# untitled.net
KiCad netlist of a schematic drawn in EAGLE
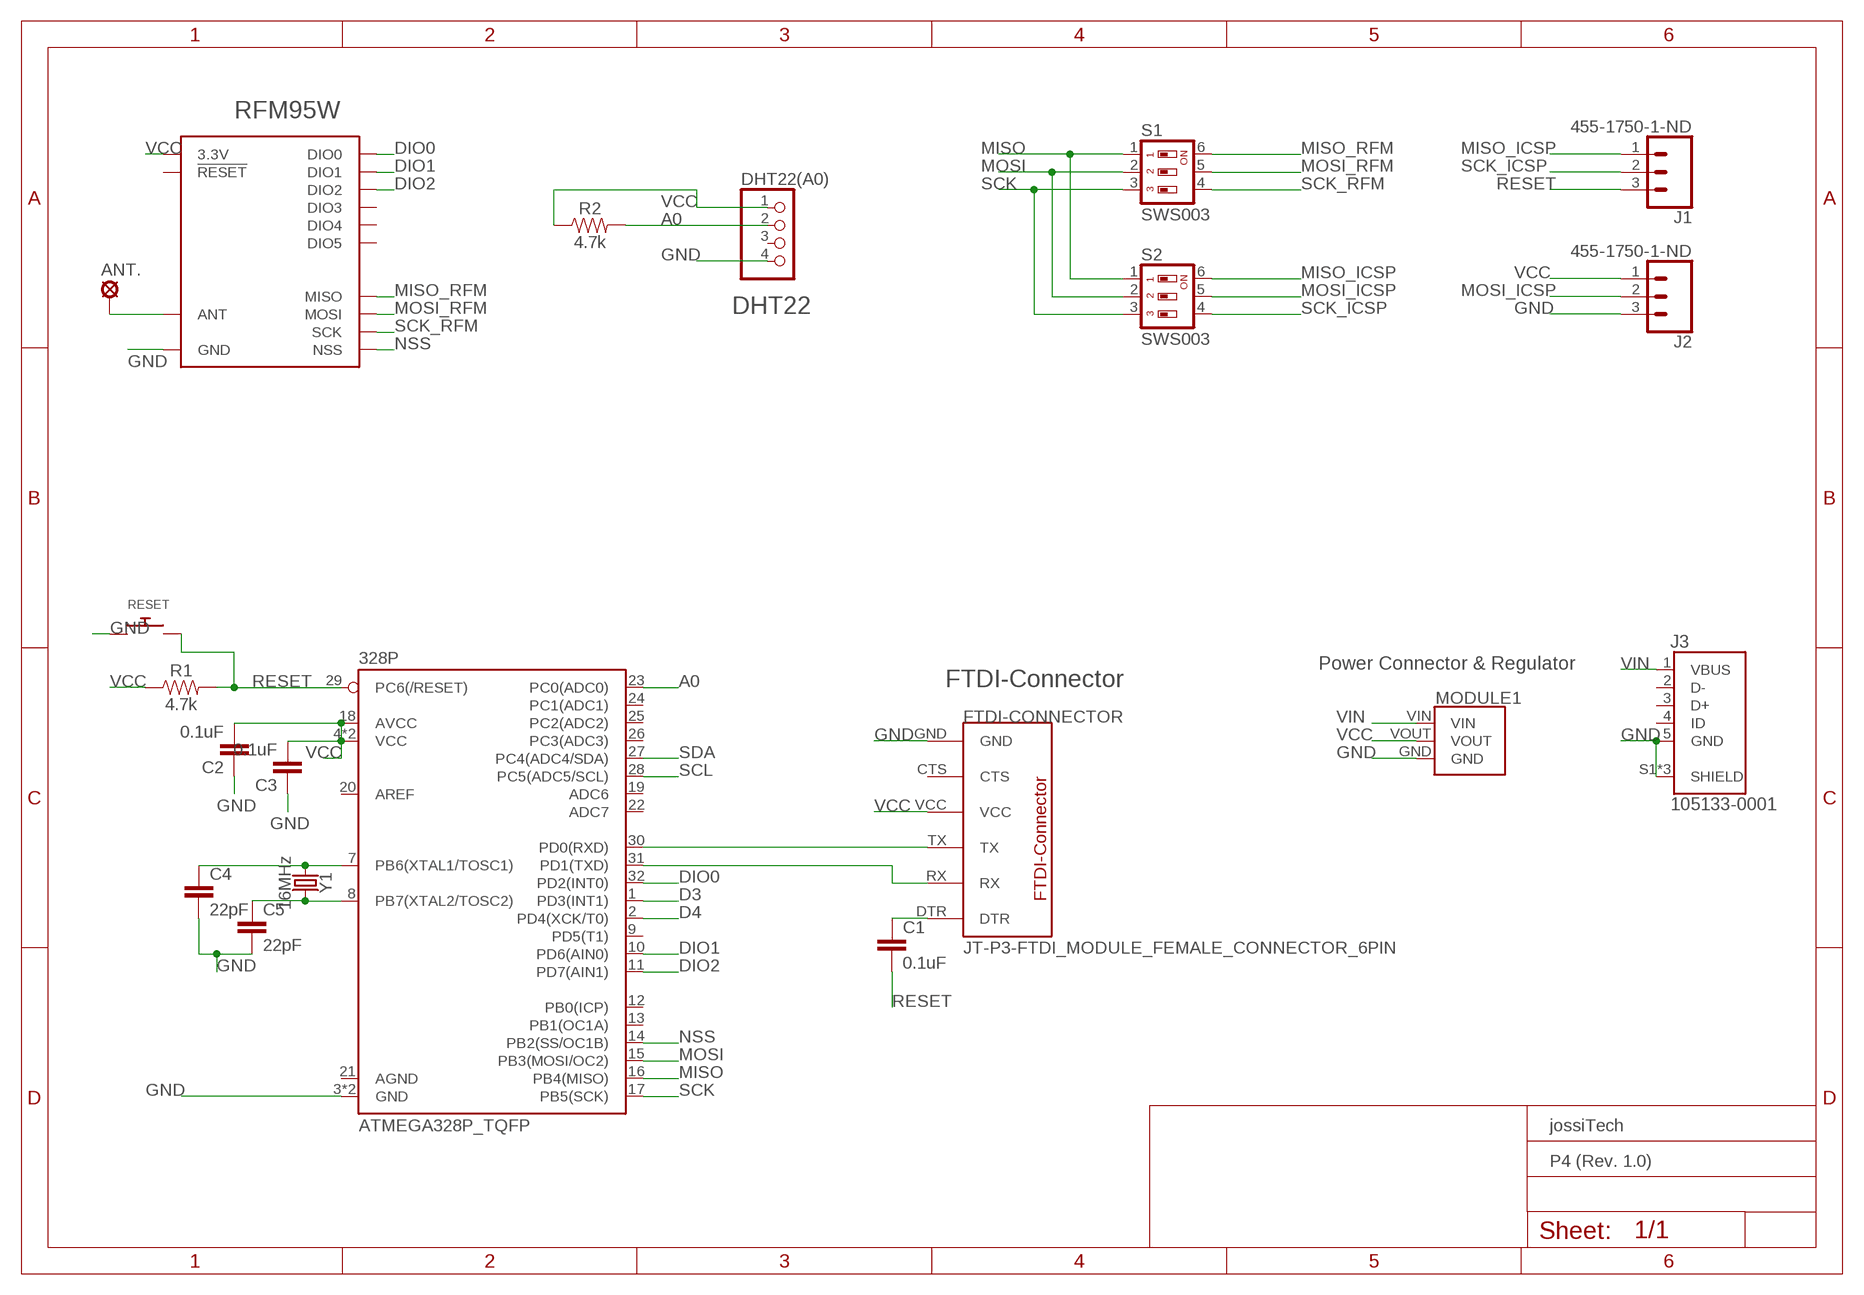
[diagram p0: schematic, sheet 1]

(export (version "E")
  (design (tool "Eeschema 10.0.6"))
  (components
    (comp (ref "328P")
      (value "ATMEGA328P_TQFP")
      (footprint "eagle-import:TQFP32-08")
      (libsource (lib "eagle-import") (part "ATMEGA328P_TQFP"))
    )
    (comp (ref "ANT.")
      (value "LSP11")
      (footprint "eagle-import:LSP11")
      (libsource (lib "eagle-import") (part "LSP11"))
    )
    (comp (ref "C1")
      (value "0.1uF")
      (footprint "eagle-import:0603")
      (libsource (lib "eagle-import") (part "0.1UF-0603-25V-(+80/-20%)"))
    )
    (comp (ref "C2")
      (value "0.1uF")
      (footprint "eagle-import:0603")
      (libsource (lib "eagle-import") (part "0.1UF-0603-25V-(+80/-20%)"))
    )
    (comp (ref "C3")
      (value "0.1uF")
      (footprint "eagle-import:0603")
      (libsource (lib "eagle-import") (part "0.1UF-0603-25V-(+80/-20%)"))
    )
    (comp (ref "C4")
      (value "22pF")
      (footprint "eagle-import:0603")
      (libsource (lib "eagle-import") (part "22PF-0603-50V-5%"))
    )
    (comp (ref "C5")
      (value "22pF")
      (footprint "eagle-import:0603")
      (libsource (lib "eagle-import") (part "22PF-0603-50V-5%"))
    )
    (comp (ref "DHT22(A0)")
      (value "PINHD-1X4")
      (footprint "eagle-import:1X04")
      (libsource (lib "eagle-import") (part "PINHD-1X4"))
    )
    (comp (ref "FTDI-CONNECTOR")
      (value "JT-P3-FTDI_MODULE_FEMALE_CONNECTOR_6PIN")
      (footprint "eagle-import:JT-P3-FTDI_MODULE_FEMALE_CONNECTOR_6PIN")
      (libsource (lib "eagle-import") (part "JT-P3-FTDI_MODULE_FEMALE_CONNECTOR_6PIN"))
    )
    (comp (ref "J1")
      (value "455-1750-1-ND")
      (footprint "eagle-import:1X03")
      (libsource (lib "eagle-import") (part "CONN_03"))
    )
    (comp (ref "J2")
      (value "455-1750-1-ND")
      (footprint "eagle-import:1X03")
      (libsource (lib "eagle-import") (part "CONN_03"))
    )
    (comp (ref "J3")
      (value "105133-0001")
      (footprint "eagle-import:MOLEX_105133-0001")
      (fields (field (name "MF") "Molex"))
      (libsource (lib "eagle-import") (part "105133-0001"))
    )
    (comp (ref "MODULE1")
      (value "JT-P3-VOLTAGEREGULATOR")
      (footprint "eagle-import:JT-P3-VOLTAGEREGULATOR")
      (libsource (lib "eagle-import") (part "JT-P3-VOLTAGEREGULATOR"))
    )
    (comp (ref "R1")
      (value "4.7k")
      (footprint "eagle-import:0603")
      (libsource (lib "eagle-import") (part "4.7KOHM-0603-1/10W-1%"))
    )
    (comp (ref "R2")
      (value "4.7k")
      (footprint "eagle-import:0603")
      (libsource (lib "eagle-import") (part "4.7KOHM-0603-1/10W-1%"))
    )
    (comp (ref "RESET")
      (value "SWITCH_PUSHBUTTONEVQ-PE")
      (footprint "eagle-import:TACT_PANA-EVQ")
      (libsource (lib "eagle-import") (part "SWITCH_PUSHBUTTONEVQ-PE"))
    )
    (comp (ref "S1")
      (value "SWS003")
      (footprint "eagle-import:SMS-003")
      (libsource (lib "eagle-import") (part "SWS003"))
    )
    (comp (ref "S2")
      (value "SWS003")
      (footprint "eagle-import:SMS-003")
      (libsource (lib "eagle-import") (part "SWS003"))
    )
    (comp (ref "U2")
      (value "RFM95W")
      (footprint "eagle-import:RFM95_96_97_98W")
      (libsource (lib "eagle-import") (part "RFM95W"))
    )
    (comp (ref "Y1")
      (value "16MHz")
      (footprint "eagle-import:CRYSTAL-SMD-5X3.2-4PAD")
      (libsource (lib "eagle-import") (part "CRYSTAL-16MHZSMD-5X3.2"))
    )
  )
  (nets
    (net (code "1") (name "/A0") (class "Default")
      (node (ref "328P") (pin "23") (pinfunction "PC0(ADC0)_23") (pintype "bidirectional"))
      (node (ref "DHT22(A0)") (pin "2") (pinfunction "2_2") (pintype "passive"))
      (node (ref "R2") (pin "2") (pinfunction "2_2") (pintype "passive"))
    )
    (net (code "2") (name "/D3") (class "Default")
      (node (ref "328P") (pin "1") (pinfunction "PD3(INT1)_1") (pintype "bidirectional"))
    )
    (net (code "3") (name "/D4") (class "Default")
      (node (ref "328P") (pin "2") (pinfunction "PD4(XCK/T0)_2") (pintype "bidirectional"))
    )
    (net (code "4") (name "/DIO0") (class "Default")
      (node (ref "328P") (pin "32") (pinfunction "PD2(INT0)_32") (pintype "bidirectional"))
      (node (ref "U2") (pin "DIO0") (pinfunction "DIO0_DIO0") (pintype "bidirectional"))
    )
    (net (code "5") (name "/DIO1") (class "Default")
      (node (ref "328P") (pin "10") (pinfunction "PD6(AIN0)_10") (pintype "bidirectional"))
      (node (ref "U2") (pin "DIO1") (pinfunction "DIO1_DIO1") (pintype "bidirectional"))
    )
    (net (code "6") (name "/DIO2") (class "Default")
      (node (ref "328P") (pin "11") (pinfunction "PD7(AIN1)_11") (pintype "bidirectional"))
      (node (ref "U2") (pin "DIO2") (pinfunction "DIO2_DIO2") (pintype "bidirectional"))
    )
    (net (code "7") (name "/GND") (class "Default")
      (node (ref "328P") (pin "3") (pinfunction "GND_3") (pintype "bidirectional"))
      (node (ref "328P") (pin "5") (pinfunction "GND_5") (pintype "bidirectional"))
      (node (ref "C2") (pin "1") (pinfunction "1_1") (pintype "passive"))
      (node (ref "C3") (pin "1") (pinfunction "1_1") (pintype "passive"))
      (node (ref "C4") (pin "2") (pinfunction "2_2") (pintype "passive"))
      (node (ref "C5") (pin "2") (pinfunction "2_2") (pintype "passive"))
      (node (ref "DHT22(A0)") (pin "4") (pinfunction "4_4") (pintype "passive"))
      (node (ref "FTDI-CONNECTOR") (pin "GND") (pinfunction "GND_GND") (pintype "bidirectional"))
      (node (ref "J2") (pin "3") (pinfunction "3_3") (pintype "passive"))
      (node (ref "J3") (pin "5") (pinfunction "GND_5") (pintype "power_in"))
      (node (ref "J3") (pin "S1") (pinfunction "SHIELD_S1") (pintype "passive"))
      (node (ref "J3") (pin "S2") (pinfunction "SHIELD_S2") (pintype "passive"))
      (node (ref "J3") (pin "S3") (pinfunction "SHIELD_S3") (pintype "passive"))
      (node (ref "MODULE1") (pin "GND") (pinfunction "GND_GND") (pintype "bidirectional"))
      (node (ref "RESET") (pin "P$1") (pinfunction "P$1_P$1") (pintype "passive"))
      (node (ref "U2") (pin "GND@1") (pinfunction "GND_GND@1") (pintype "bidirectional"))
      (node (ref "U2") (pin "GND@2") (pinfunction "GND_GND@2") (pintype "bidirectional"))
      (node (ref "U2") (pin "GND@3") (pinfunction "GND_GND@3") (pintype "bidirectional"))
    )
    (net (code "8") (name "/MISO") (class "Default")
      (node (ref "328P") (pin "16") (pinfunction "PB4(MISO)_16") (pintype "bidirectional"))
      (node (ref "S1") (pin "1") (pinfunction "1_1") (pintype "passive"))
      (node (ref "S2") (pin "1") (pinfunction "1_1") (pintype "passive"))
    )
    (net (code "9") (name "/MISO_ICSP") (class "Default")
      (node (ref "J1") (pin "1") (pinfunction "1_1") (pintype "passive"))
      (node (ref "S2") (pin "6") (pinfunction "6_6") (pintype "passive"))
    )
    (net (code "10") (name "/MISO_RFM") (class "Default")
      (node (ref "S1") (pin "6") (pinfunction "6_6") (pintype "passive"))
      (node (ref "U2") (pin "MISO") (pinfunction "MISO_MISO") (pintype "bidirectional"))
    )
    (net (code "11") (name "/MOSI") (class "Default")
      (node (ref "328P") (pin "15") (pinfunction "PB3(MOSI/OC2)_15") (pintype "bidirectional"))
      (node (ref "S1") (pin "2") (pinfunction "2_2") (pintype "passive"))
      (node (ref "S2") (pin "2") (pinfunction "2_2") (pintype "passive"))
    )
    (net (code "12") (name "/MOSI_ICSP") (class "Default")
      (node (ref "J2") (pin "2") (pinfunction "2_2") (pintype "passive"))
      (node (ref "S2") (pin "5") (pinfunction "5_5") (pintype "passive"))
    )
    (net (code "13") (name "/MOSI_RFM") (class "Default")
      (node (ref "S1") (pin "5") (pinfunction "5_5") (pintype "passive"))
      (node (ref "U2") (pin "MOSI") (pinfunction "MOSI_MOSI") (pintype "bidirectional"))
    )
    (net (code "14") (name "/NSS") (class "Default")
      (node (ref "328P") (pin "14") (pinfunction "PB2(SS/OC1B)_14") (pintype "bidirectional"))
      (node (ref "U2") (pin "NSS") (pinfunction "NSS_NSS") (pintype "bidirectional"))
    )
    (net (code "15") (name "/RESET") (class "Default")
      (node (ref "328P") (pin "29") (pinfunction "PC6(/RESET)_29") (pintype "bidirectional"))
      (node (ref "C1") (pin "2") (pinfunction "2_2") (pintype "passive"))
      (node (ref "J1") (pin "3") (pinfunction "3_3") (pintype "passive"))
      (node (ref "R1") (pin "2") (pinfunction "2_2") (pintype "passive"))
      (node (ref "RESET") (pin "P$2") (pinfunction "P$2_P$2") (pintype "passive"))
    )
    (net (code "16") (name "/SCK") (class "Default")
      (node (ref "328P") (pin "17") (pinfunction "PB5(SCK)_17") (pintype "bidirectional"))
      (node (ref "S1") (pin "3") (pinfunction "3_3") (pintype "passive"))
      (node (ref "S2") (pin "3") (pinfunction "3_3") (pintype "passive"))
    )
    (net (code "17") (name "/SCK_ICSP") (class "Default")
      (node (ref "J1") (pin "2") (pinfunction "2_2") (pintype "passive"))
      (node (ref "S2") (pin "4") (pinfunction "4_4") (pintype "passive"))
    )
    (net (code "18") (name "/SCK_RFM") (class "Default")
      (node (ref "S1") (pin "4") (pinfunction "4_4") (pintype "passive"))
      (node (ref "U2") (pin "SCK") (pinfunction "SCK_SCK") (pintype "bidirectional"))
    )
    (net (code "19") (name "/SCL") (class "Default")
      (node (ref "328P") (pin "28") (pinfunction "PC5(ADC5/SCL)_28") (pintype "bidirectional"))
    )
    (net (code "20") (name "/SDA") (class "Default")
      (node (ref "328P") (pin "27") (pinfunction "PC4(ADC4/SDA)_27") (pintype "bidirectional"))
    )
    (net (code "21") (name "/VCC") (class "Default")
      (node (ref "328P") (pin "18") (pinfunction "AVCC_18") (pintype "bidirectional"))
      (node (ref "328P") (pin "4") (pinfunction "VCC_4") (pintype "bidirectional"))
      (node (ref "328P") (pin "6") (pinfunction "VCC_6") (pintype "bidirectional"))
      (node (ref "C2") (pin "2") (pinfunction "2_2") (pintype "passive"))
      (node (ref "C3") (pin "2") (pinfunction "2_2") (pintype "passive"))
      (node (ref "DHT22(A0)") (pin "1") (pinfunction "1_1") (pintype "passive"))
      (node (ref "FTDI-CONNECTOR") (pin "VCC") (pinfunction "VCC_VCC") (pintype "bidirectional"))
      (node (ref "J2") (pin "1") (pinfunction "1_1") (pintype "passive"))
      (node (ref "MODULE1") (pin "VOUT") (pinfunction "VOUT_VOUT") (pintype "bidirectional"))
      (node (ref "R1") (pin "1") (pinfunction "1_1") (pintype "passive"))
      (node (ref "R2") (pin "1") (pinfunction "1_1") (pintype "passive"))
      (node (ref "U2") (pin "3.3V") (pinfunction "3.3V_3.3V") (pintype "bidirectional"))
    )
    (net (code "22") (name "/VIN") (class "Default")
      (node (ref "J3") (pin "1") (pinfunction "VBUS_1") (pintype "power_in"))
      (node (ref "MODULE1") (pin "VIN") (pinfunction "VIN_VIN") (pintype "bidirectional"))
    )
    (net (code "23") (name "Net-(328P-PB6(XTAL1{slash}TOSC1))") (class "Default")
      (node (ref "328P") (pin "7") (pinfunction "PB6(XTAL1/TOSC1)_7") (pintype "bidirectional"))
      (node (ref "C4") (pin "1") (pinfunction "1_1") (pintype "passive"))
      (node (ref "Y1") (pin "1") (pinfunction "1_1") (pintype "passive"))
    )
    (net (code "24") (name "Net-(328P-PB7(XTAL2{slash}TOSC2))") (class "Default")
      (node (ref "328P") (pin "8") (pinfunction "PB7(XTAL2/TOSC2)_8") (pintype "bidirectional"))
      (node (ref "C5") (pin "1") (pinfunction "1_1") (pintype "passive"))
      (node (ref "Y1") (pin "3") (pinfunction "2_3") (pintype "passive"))
    )
    (net (code "25") (name "Net-(328P-PD0(RXD))") (class "Default")
      (node (ref "328P") (pin "30") (pinfunction "PD0(RXD)_30") (pintype "bidirectional"))
      (node (ref "FTDI-CONNECTOR") (pin "TX") (pinfunction "TX_TX") (pintype "bidirectional"))
    )
    (net (code "26") (name "Net-(328P-PD1(TXD))") (class "Default")
      (node (ref "328P") (pin "31") (pinfunction "PD1(TXD)_31") (pintype "bidirectional"))
      (node (ref "FTDI-CONNECTOR") (pin "RX") (pinfunction "RX_RX") (pintype "bidirectional"))
    )
    (net (code "27") (name "Net-(ANT.-PadMP)") (class "Default")
      (node (ref "ANT.") (pin "MP") (pinfunction "MP_MP") (pintype "passive"))
      (node (ref "U2") (pin "ANT") (pinfunction "ANT_ANT") (pintype "bidirectional"))
    )
    (net (code "28") (name "Net-(C1-Pad1)") (class "Default")
      (node (ref "C1") (pin "1") (pinfunction "1_1") (pintype "passive"))
      (node (ref "FTDI-CONNECTOR") (pin "DTR") (pinfunction "DTR_DTR") (pintype "bidirectional"))
    )
    (net (code "29") (name "unconnected-(328P-ADC6-Pad19)") (class "Default")
      (node (ref "328P") (pin "19") (pinfunction "ADC6_19") (pintype "bidirectional"))
    )
    (net (code "30") (name "unconnected-(328P-ADC7-Pad22)") (class "Default")
      (node (ref "328P") (pin "22") (pinfunction "ADC7_22") (pintype "bidirectional"))
    )
    (net (code "31") (name "unconnected-(328P-AGND-Pad21)") (class "Default")
      (node (ref "328P") (pin "21") (pinfunction "AGND_21") (pintype "bidirectional"))
    )
    (net (code "32") (name "unconnected-(328P-AREF-Pad20)") (class "Default")
      (node (ref "328P") (pin "20") (pinfunction "AREF_20") (pintype "bidirectional"))
    )
    (net (code "33") (name "unconnected-(328P-PB0(ICP)-Pad12)") (class "Default")
      (node (ref "328P") (pin "12") (pinfunction "PB0(ICP)_12") (pintype "bidirectional"))
    )
    (net (code "34") (name "unconnected-(328P-PB1(OC1A)-Pad13)") (class "Default")
      (node (ref "328P") (pin "13") (pinfunction "PB1(OC1A)_13") (pintype "bidirectional"))
    )
    (net (code "35") (name "unconnected-(328P-PC1(ADC1)-Pad24)") (class "Default")
      (node (ref "328P") (pin "24") (pinfunction "PC1(ADC1)_24") (pintype "bidirectional"))
    )
    (net (code "36") (name "unconnected-(328P-PC2(ADC2)-Pad25)") (class "Default")
      (node (ref "328P") (pin "25") (pinfunction "PC2(ADC2)_25") (pintype "bidirectional"))
    )
    (net (code "37") (name "unconnected-(328P-PC3(ADC3)-Pad26)") (class "Default")
      (node (ref "328P") (pin "26") (pinfunction "PC3(ADC3)_26") (pintype "bidirectional"))
    )
    (net (code "38") (name "unconnected-(328P-PD5(T1)-Pad9)") (class "Default")
      (node (ref "328P") (pin "9") (pinfunction "PD5(T1)_9") (pintype "bidirectional"))
    )
    (net (code "39") (name "unconnected-(DHT22(A0)-Pad3)") (class "Default")
      (node (ref "DHT22(A0)") (pin "3") (pinfunction "3_3") (pintype "passive"))
    )
    (net (code "40") (name "unconnected-(FTDI-CONNECTOR-PadCTS)") (class "Default")
      (node (ref "FTDI-CONNECTOR") (pin "CTS") (pinfunction "CTS_CTS") (pintype "bidirectional"))
    )
    (net (code "41") (name "unconnected-(J3-D+-Pad3)") (class "Default")
      (node (ref "J3") (pin "3") (pinfunction "D+_3") (pintype "bidirectional"))
    )
    (net (code "42") (name "unconnected-(J3-D--Pad2)") (class "Default")
      (node (ref "J3") (pin "2") (pinfunction "D-_2") (pintype "bidirectional"))
    )
    (net (code "43") (name "unconnected-(J3-ID-Pad4)") (class "Default")
      (node (ref "J3") (pin "4") (pinfunction "ID_4") (pintype "input"))
    )
    (net (code "44") (name "unconnected-(U2-PadDIO3)") (class "Default")
      (node (ref "U2") (pin "DIO3") (pinfunction "DIO3_DIO3") (pintype "bidirectional"))
    )
    (net (code "45") (name "unconnected-(U2-PadDIO4)") (class "Default")
      (node (ref "U2") (pin "DIO4") (pinfunction "DIO4_DIO4") (pintype "bidirectional"))
    )
    (net (code "46") (name "unconnected-(U2-PadDIO5)") (class "Default")
      (node (ref "U2") (pin "DIO5") (pinfunction "DIO5_DIO5") (pintype "bidirectional"))
    )
    (net (code "47") (name "unconnected-(U2-~{RESET}-Pad!RESET)") (class "Default")
      (node (ref "U2") (pin "!RESET") (pinfunction "~{RESET}_!RESET") (pintype "bidirectional"))
    )
  )
)
